# STS_01.net
KiCad netlist of a schematic drawn in Altium Designer
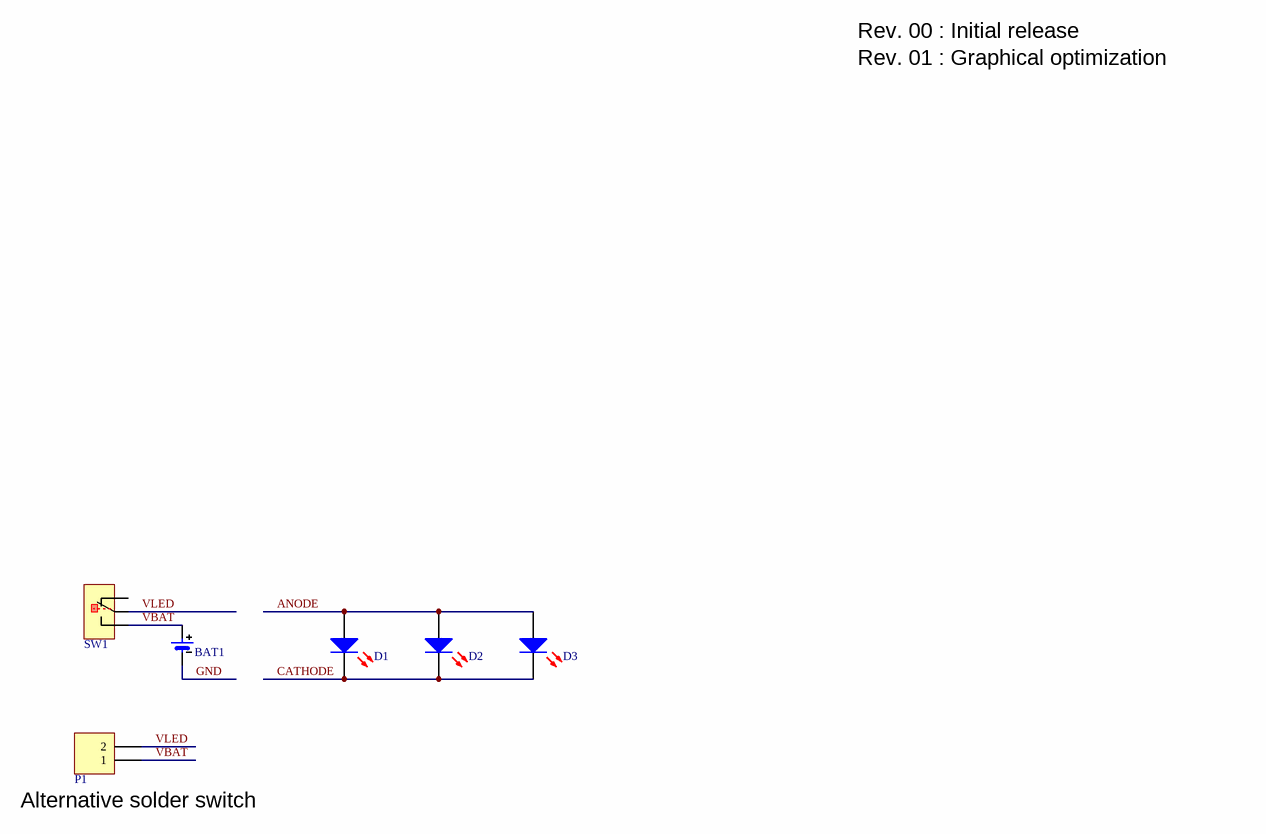
[diagram p0: STS.01.SchDoc]

(export (version "E")
  (design (tool "Eeschema 10.0.6"))
  (components
    (comp (ref "BAT1")
      (value "CR2032 SMD Battery Holder")
      (footprint "BAT_CR2032_KEY_1060")
      (description "=Description")
      (libsource (lib "Phyx_Components") (part "BAT_2"))
    )
    (comp (ref "D1")
      (value "Default 5mm Red LED")
      (footprint "LED_5MM_RD")
      (description "=Description")
      (libsource (lib "Phyx_Components") (part "LED_RED"))
    )
    (comp (ref "D2")
      (value "Default 5mm Red LED")
      (footprint "LED_5MM_RD")
      (description "=Description")
      (libsource (lib "Phyx_Components") (part "LED_RED"))
    )
    (comp (ref "D3")
      (value "Default 5mm Red LED")
      (footprint "LED_5MM_RD")
      (description "=Description")
      (libsource (lib "Phyx_Components") (part "LED_RED"))
    )
    (comp (ref "P1")
      (value "Easy to solder connection")
      (footprint "SOLDER_SW_V_1MM")
      (libsource (lib "Phyx_Components") (part "Header 2"))
    )
    (comp (ref "SW1")
      (value "mini Switch 1 pole double throw right angle")
      (footprint "SK-12D07")
      (libsource (lib "Phyx_Components") (part "SW_1P2T"))
    )
  )
  (nets
    (net (code "1") (name "/ANODE") (class "Default")
      (node (ref "D1") (pin "1") (pinfunction "A_1") (pintype "passive"))
      (node (ref "D2") (pin "1") (pinfunction "A_1") (pintype "passive"))
      (node (ref "D3") (pin "1") (pinfunction "A_1") (pintype "passive"))
    )
    (net (code "2") (name "/CATHODE") (class "Default")
      (node (ref "D1") (pin "2") (pinfunction "K_2") (pintype "passive"))
      (node (ref "D2") (pin "2") (pinfunction "K_2") (pintype "passive"))
      (node (ref "D3") (pin "2") (pinfunction "K_2") (pintype "passive"))
    )
    (net (code "3") (name "/GND") (class "Default")
      (node (ref "BAT1") (pin "2") (pinfunction "2_2") (pintype "passive"))
    )
    (net (code "4") (name "/VBAT") (class "Default")
      (node (ref "BAT1") (pin "1") (pinfunction "1_1") (pintype "passive"))
      (node (ref "P1") (pin "1") (pinfunction "1_1") (pintype "passive"))
      (node (ref "SW1") (pin "3") (pinfunction "3_3") (pintype "passive"))
    )
    (net (code "5") (name "/VLED") (class "Default")
      (node (ref "P1") (pin "2") (pinfunction "2_2") (pintype "passive"))
      (node (ref "SW1") (pin "2") (pinfunction "2_2") (pintype "passive"))
    )
    (net (code "6") (name "unconnected-(SW1-Pad1)") (class "Default")
      (node (ref "SW1") (pin "1") (pinfunction "1_1") (pintype "passive"))
    )
  )
)
